# Quadcopter_PCB.net
KiCad netlist of a schematic drawn in EAGLE
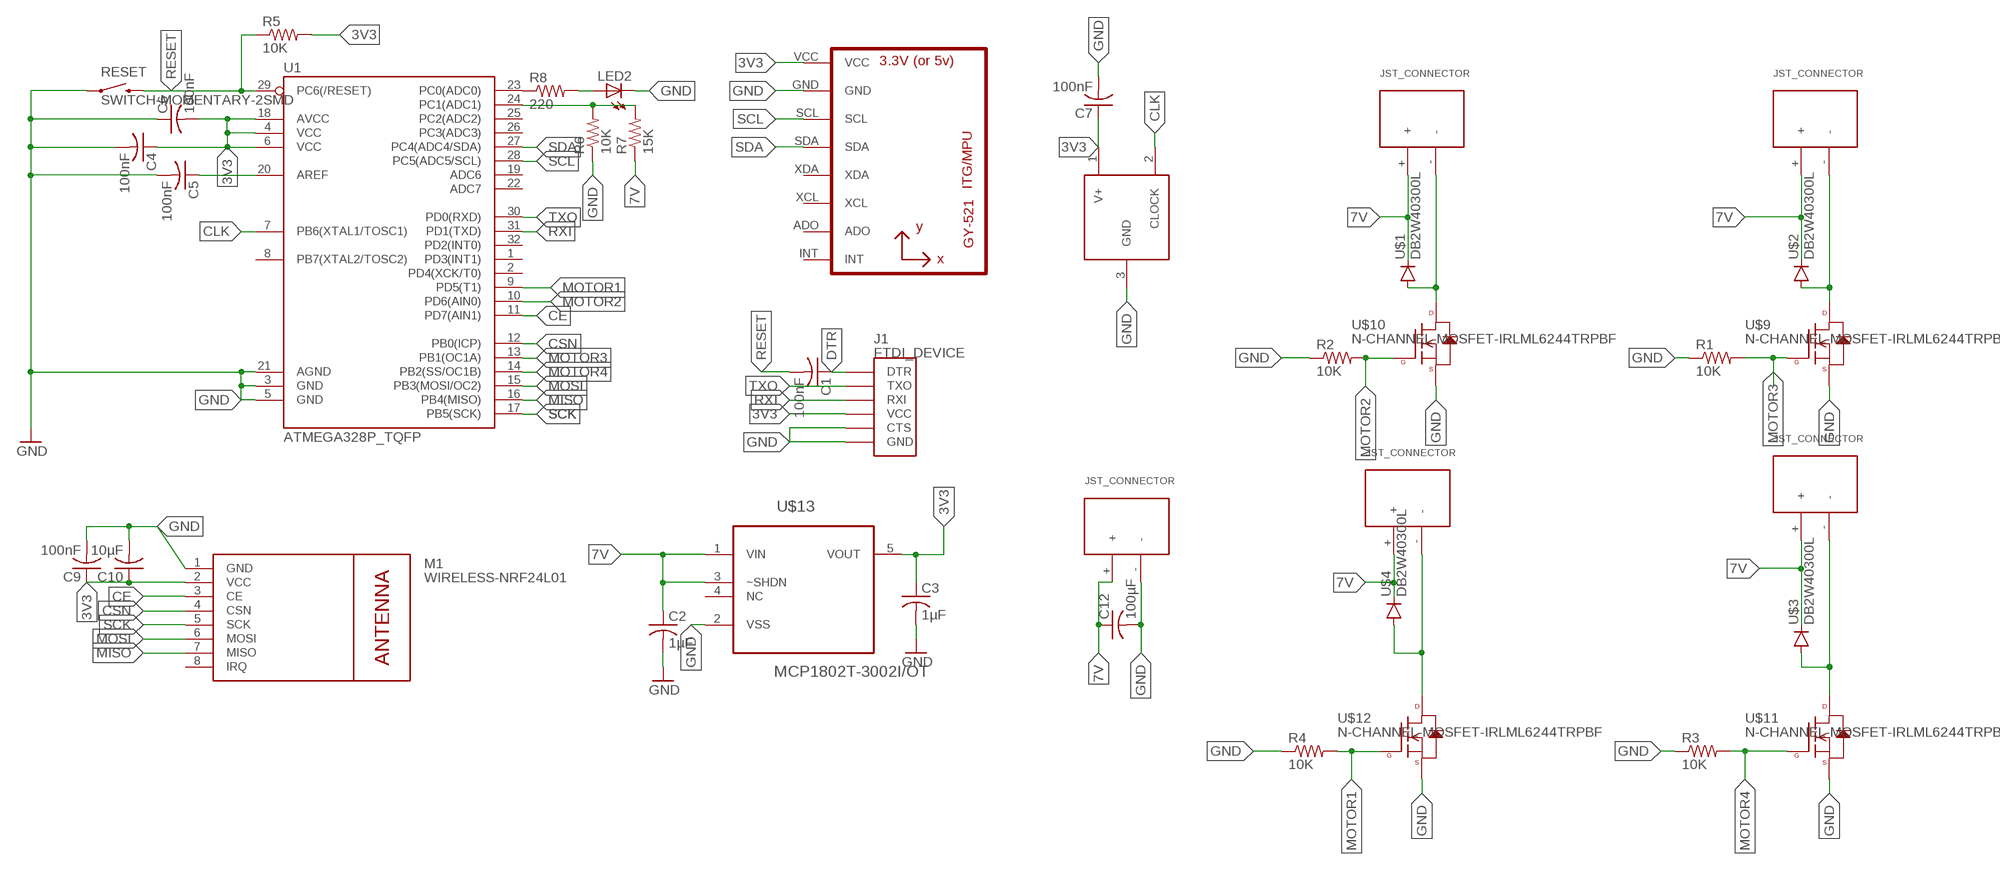
[diagram p0: schematic, sheet 1]

(export (version "E")
  (design (tool "Eeschema 10.0.6"))
  (components
    (comp (ref "AXR1")
      (value "MAX7375")
      (footprint "eagle-import:SC70-3L")
      (libsource (lib "eagle-import") (part "MAX7375"))
    )
    (comp (ref "BATTERYJSTCONNECTOR")
      (value "JST_CONNECTOR_FEMALE")
      (footprint "eagle-import:JST_CONNECTOR_FEMALE")
      (libsource (lib "eagle-import") (part "JST_CONNECTOR_FEMALE"))
    )
    (comp (ref "C1")
      (value "100nF")
      (footprint "eagle-import:C0603")
      (libsource (lib "eagle-import") (part "C-USC0603"))
    )
    (comp (ref "C2")
      (value "1µF")
      (footprint "eagle-import:C0603")
      (libsource (lib "eagle-import") (part "C-USC0603"))
    )
    (comp (ref "C3")
      (value "1µF")
      (footprint "eagle-import:C0603")
      (libsource (lib "eagle-import") (part "C-USC0603"))
    )
    (comp (ref "C4")
      (value "100nF")
      (footprint "eagle-import:C0603")
      (libsource (lib "eagle-import") (part "resistor_C-USC0603"))
    )
    (comp (ref "C5")
      (value "100nF")
      (footprint "eagle-import:C0603")
      (libsource (lib "eagle-import") (part "resistor_C-USC0603"))
    )
    (comp (ref "C6")
      (value "100nF")
      (footprint "eagle-import:C0603")
      (libsource (lib "eagle-import") (part "C-USC0603"))
    )
    (comp (ref "C7")
      (value "100nF")
      (footprint "eagle-import:C0603")
      (libsource (lib "eagle-import") (part "C-USC0603"))
    )
    (comp (ref "C9")
      (value "100nF")
      (footprint "eagle-import:C0603")
      (libsource (lib "eagle-import") (part "C-USC0603"))
    )
    (comp (ref "C10")
      (value "10µF")
      (footprint "eagle-import:C0603")
      (libsource (lib "eagle-import") (part "C-USC0603"))
    )
    (comp (ref "C12")
      (value "100µF")
      (footprint "eagle-import:C1210")
      (libsource (lib "eagle-import") (part "resistor_C-USC1210"))
    )
    (comp (ref "J1")
      (value "FTDI_DEVICE")
      (footprint "eagle-import:FTDI_DEVICE_SIDE")
      (libsource (lib "eagle-import") (part "FTDI_DEVICE"))
    )
    (comp (ref "LED2")
      (value "LEDCHIP-LED0603")
      (footprint "eagle-import:CHIP-LED0603")
      (libsource (lib "eagle-import") (part "LEDCHIP-LED0603"))
    )
    (comp (ref "M1")
      (value "WIRELESS-NRF24L01")
      (footprint "eagle-import:WIRELESS-NRF24L01")
      (libsource (lib "eagle-import") (part "WIRELESS-NRF24L01"))
    )
    (comp (ref "R1")
      (value "10K")
      (footprint "eagle-import:R0603")
      (libsource (lib "eagle-import") (part "R-US_R0603"))
    )
    (comp (ref "R2")
      (value "10K")
      (footprint "eagle-import:R0603")
      (libsource (lib "eagle-import") (part "R-US_R0603"))
    )
    (comp (ref "R3")
      (value "10K")
      (footprint "eagle-import:R0603")
      (libsource (lib "eagle-import") (part "R-US_R0603"))
    )
    (comp (ref "R4")
      (value "10K")
      (footprint "eagle-import:R0603")
      (libsource (lib "eagle-import") (part "R-US_R0603"))
    )
    (comp (ref "R5")
      (value "10K")
      (footprint "eagle-import:R0603")
      (libsource (lib "eagle-import") (part "R-US_R0603"))
    )
    (comp (ref "R6")
      (value "10K")
      (footprint "eagle-import:R0603")
      (libsource (lib "eagle-import") (part "resistor_R-US_R0603"))
    )
    (comp (ref "R7")
      (value "15K")
      (footprint "eagle-import:R0603")
      (libsource (lib "eagle-import") (part "resistor_R-US_R0603"))
    )
    (comp (ref "R8")
      (value "220")
      (footprint "eagle-import:R0603")
      (libsource (lib "eagle-import") (part "R-US_R0603"))
    )
    (comp (ref "RESET")
      (value "SWITCH-MOMENTARY-2SMD")
      (footprint "eagle-import:TACTILE-SWITCH-SMD")
      (libsource (lib "eagle-import") (part "SWITCH-MOMENTARY-2SMD"))
    )
    (comp (ref "U$1")
      (value "DB2W40300L")
      (footprint "eagle-import:MINI2-F3-B")
      (libsource (lib "eagle-import") (part "DB2W40300L"))
    )
    (comp (ref "U$2")
      (value "DB2W40300L")
      (footprint "eagle-import:MINI2-F3-B")
      (libsource (lib "eagle-import") (part "DB2W40300L"))
    )
    (comp (ref "U$3")
      (value "DB2W40300L")
      (footprint "eagle-import:MINI2-F3-B")
      (libsource (lib "eagle-import") (part "DB2W40300L"))
    )
    (comp (ref "U$4")
      (value "DB2W40300L")
      (footprint "eagle-import:MINI2-F3-B")
      (libsource (lib "eagle-import") (part "DB2W40300L"))
    )
    (comp (ref "U$5")
      (value "JST_CONNECTOR_FEMALE")
      (footprint "eagle-import:JST_CONNECTOR_FEMALE")
      (libsource (lib "eagle-import") (part "JST_CONNECTOR_FEMALE"))
    )
    (comp (ref "U$6")
      (value "JST_CONNECTOR_FEMALE")
      (footprint "eagle-import:JST_CONNECTOR_FEMALE")
      (libsource (lib "eagle-import") (part "JST_CONNECTOR_FEMALE"))
    )
    (comp (ref "U$7")
      (value "JST_CONNECTOR_FEMALE")
      (footprint "eagle-import:JST_CONNECTOR_FEMALE")
      (libsource (lib "eagle-import") (part "JST_CONNECTOR_FEMALE"))
    )
    (comp (ref "U$8")
      (value "JST_CONNECTOR_FEMALE")
      (footprint "eagle-import:JST_CONNECTOR_FEMALE")
      (libsource (lib "eagle-import") (part "JST_CONNECTOR_FEMALE"))
    )
    (comp (ref "U$9")
      (value "N-CHANNEL-MOSFET-IRLML6244TRPBF")
      (footprint "eagle-import:SOT23-3")
      (libsource (lib "eagle-import") (part "N-CHANNEL-MOSFET-IRLML6244TRPBF"))
    )
    (comp (ref "U$10")
      (value "N-CHANNEL-MOSFET-IRLML6244TRPBF")
      (footprint "eagle-import:SOT23-3")
      (libsource (lib "eagle-import") (part "N-CHANNEL-MOSFET-IRLML6244TRPBF"))
    )
    (comp (ref "U$11")
      (value "N-CHANNEL-MOSFET-IRLML6244TRPBF")
      (footprint "eagle-import:SOT23-3")
      (libsource (lib "eagle-import") (part "N-CHANNEL-MOSFET-IRLML6244TRPBF"))
    )
    (comp (ref "U$12")
      (value "N-CHANNEL-MOSFET-IRLML6244TRPBF")
      (footprint "eagle-import:SOT23-3")
      (libsource (lib "eagle-import") (part "N-CHANNEL-MOSFET-IRLML6244TRPBF"))
    )
    (comp (ref "U$13")
      (value "MCP1802T-3002I/OT")
      (footprint "eagle-import:SOT95P270X145-5N")
      (libsource (lib "eagle-import") (part "MCP1802T-3002I/OT"))
    )
    (comp (ref "U1")
      (value "ATMEGA328P_TQFP")
      (footprint "eagle-import:TQFP32-08")
      (libsource (lib "eagle-import") (part "ATMEGA328P_TQFP"))
    )
    (comp (ref "U2")
      (value "GY-521MPU6050")
      (footprint "eagle-import:GY-521")
      (libsource (lib "eagle-import") (part "GY-521MPU6050"))
    )
  )
  (nets
    (net (code "1") (name "3V3") (class "Default")
      (node (ref "AXR1") (pin "1") (pinfunction "V+_1") (pintype "bidirectional"))
      (node (ref "C10") (pin "1") (pinfunction "1_1") (pintype "passive"))
      (node (ref "C3") (pin "1") (pinfunction "1_1") (pintype "passive"))
      (node (ref "C4") (pin "1") (pinfunction "1_1") (pintype "passive"))
      (node (ref "C5") (pin "1") (pinfunction "1_1") (pintype "passive"))
      (node (ref "C6") (pin "2") (pinfunction "2_2") (pintype "passive"))
      (node (ref "C7") (pin "1") (pinfunction "1_1") (pintype "passive"))
      (node (ref "C9") (pin "1") (pinfunction "1_1") (pintype "passive"))
      (node (ref "J1") (pin "P$4") (pinfunction "VCC_P$4") (pintype "bidirectional"))
      (node (ref "M1") (pin "2") (pinfunction "VCC_2") (pintype "power_in"))
      (node (ref "R5") (pin "2") (pinfunction "2_2") (pintype "passive"))
      (node (ref "U$13") (pin "5") (pinfunction "VOUT_5") (pintype "output"))
      (node (ref "U1") (pin "18") (pinfunction "AVCC_18") (pintype "bidirectional"))
      (node (ref "U1") (pin "20") (pinfunction "AREF_20") (pintype "bidirectional"))
      (node (ref "U1") (pin "4") (pinfunction "VCC_4") (pintype "bidirectional"))
      (node (ref "U1") (pin "6") (pinfunction "VCC_6") (pintype "bidirectional"))
      (node (ref "U2") (pin "VCC") (pinfunction "VCC_VCC") (pintype "bidirectional"))
    )
    (net (code "2") (name "7V") (class "Default")
      (node (ref "BATTERYJSTCONNECTOR") (pin "+") (pinfunction "+_+") (pintype "bidirectional"))
      (node (ref "C12") (pin "1") (pinfunction "1_1") (pintype "passive"))
      (node (ref "C2") (pin "1") (pinfunction "1_1") (pintype "passive"))
      (node (ref "R7") (pin "1") (pinfunction "1_1") (pintype "passive"))
      (node (ref "U$1") (pin "NEG") (pinfunction "GPIN_NEG") (pintype "passive"))
      (node (ref "U$13") (pin "1") (pinfunction "VIN_1") (pintype "power_in"))
      (node (ref "U$13") (pin "3") (pinfunction "~{SHDN}_3") (pintype "input"))
      (node (ref "U$2") (pin "NEG") (pinfunction "GPIN_NEG") (pintype "passive"))
      (node (ref "U$3") (pin "NEG") (pinfunction "GPIN_NEG") (pintype "passive"))
      (node (ref "U$4") (pin "NEG") (pinfunction "GPIN_NEG") (pintype "passive"))
      (node (ref "U$5") (pin "+") (pinfunction "+_+") (pintype "bidirectional"))
      (node (ref "U$6") (pin "+") (pinfunction "+_+") (pintype "bidirectional"))
      (node (ref "U$7") (pin "+") (pinfunction "+_+") (pintype "bidirectional"))
      (node (ref "U$8") (pin "+") (pinfunction "+_+") (pintype "bidirectional"))
    )
    (net (code "3") (name "CE") (class "Default")
      (node (ref "M1") (pin "3") (pinfunction "CE_3") (pintype "bidirectional"))
      (node (ref "U1") (pin "11") (pinfunction "PD7(AIN1)_11") (pintype "bidirectional"))
    )
    (net (code "4") (name "CLK") (class "Default")
      (node (ref "AXR1") (pin "2") (pinfunction "CLOCK_2") (pintype "bidirectional"))
      (node (ref "U1") (pin "7") (pinfunction "PB6(XTAL1/TOSC1)_7") (pintype "bidirectional"))
    )
    (net (code "5") (name "CSN") (class "Default")
      (node (ref "M1") (pin "4") (pinfunction "CSN_4") (pintype "bidirectional"))
      (node (ref "U1") (pin "12") (pinfunction "PB0(ICP)_12") (pintype "bidirectional"))
    )
    (net (code "6") (name "DTR") (class "Default")
      (node (ref "C1") (pin "1") (pinfunction "1_1") (pintype "passive"))
      (node (ref "J1") (pin "P$1") (pinfunction "DTR_P$1") (pintype "bidirectional"))
    )
    (net (code "7") (name "GND") (class "Default")
      (node (ref "AXR1") (pin "3") (pinfunction "GND_3") (pintype "bidirectional"))
      (node (ref "BATTERYJSTCONNECTOR") (pin "-") (pinfunction "-_-") (pintype "bidirectional"))
      (node (ref "C10") (pin "2") (pinfunction "2_2") (pintype "passive"))
      (node (ref "C12") (pin "2") (pinfunction "2_2") (pintype "passive"))
      (node (ref "C2") (pin "2") (pinfunction "2_2") (pintype "passive"))
      (node (ref "C3") (pin "2") (pinfunction "2_2") (pintype "passive"))
      (node (ref "C4") (pin "2") (pinfunction "2_2") (pintype "passive"))
      (node (ref "C5") (pin "2") (pinfunction "2_2") (pintype "passive"))
      (node (ref "C6") (pin "1") (pinfunction "1_1") (pintype "passive"))
      (node (ref "C7") (pin "2") (pinfunction "2_2") (pintype "passive"))
      (node (ref "C9") (pin "2") (pinfunction "2_2") (pintype "passive"))
      (node (ref "J1") (pin "P$5") (pinfunction "CTS_P$5") (pintype "bidirectional"))
      (node (ref "J1") (pin "P$6") (pinfunction "GND_P$6") (pintype "bidirectional"))
      (node (ref "LED2") (pin "C") (pinfunction "C_C") (pintype "passive"))
      (node (ref "M1") (pin "1") (pinfunction "GND_1") (pintype "power_in"))
      (node (ref "R1") (pin "1") (pinfunction "1_1") (pintype "passive"))
      (node (ref "R2") (pin "1") (pinfunction "1_1") (pintype "passive"))
      (node (ref "R3") (pin "1") (pinfunction "1_1") (pintype "passive"))
      (node (ref "R4") (pin "1") (pinfunction "1_1") (pintype "passive"))
      (node (ref "R6") (pin "1") (pinfunction "1_1") (pintype "passive"))
      (node (ref "RESET") (pin "1") (pinfunction "1_1") (pintype "passive"))
      (node (ref "U$10") (pin "2") (pinfunction "S_2") (pintype "passive"))
      (node (ref "U$11") (pin "2") (pinfunction "S_2") (pintype "passive"))
      (node (ref "U$12") (pin "2") (pinfunction "S_2") (pintype "passive"))
      (node (ref "U$13") (pin "2") (pinfunction "VSS_2") (pintype "passive"))
      (node (ref "U$9") (pin "2") (pinfunction "S_2") (pintype "passive"))
      (node (ref "U1") (pin "21") (pinfunction "AGND_21") (pintype "bidirectional"))
      (node (ref "U1") (pin "3") (pinfunction "GND_3") (pintype "bidirectional"))
      (node (ref "U1") (pin "5") (pinfunction "GND_5") (pintype "bidirectional"))
      (node (ref "U2") (pin "GND") (pinfunction "GND_GND") (pintype "bidirectional"))
    )
    (net (code "8") (name "MISO") (class "Default")
      (node (ref "M1") (pin "7") (pinfunction "MISO_7") (pintype "bidirectional"))
      (node (ref "U1") (pin "16") (pinfunction "PB4(MISO)_16") (pintype "bidirectional"))
    )
    (net (code "9") (name "MOSI") (class "Default")
      (node (ref "M1") (pin "6") (pinfunction "MOSI_6") (pintype "bidirectional"))
      (node (ref "U1") (pin "15") (pinfunction "PB3(MOSI/OC2)_15") (pintype "bidirectional"))
    )
    (net (code "10") (name "MOTOR1") (class "Default")
      (node (ref "R4") (pin "2") (pinfunction "2_2") (pintype "passive"))
      (node (ref "U$12") (pin "1") (pinfunction "G_1") (pintype "passive"))
      (node (ref "U1") (pin "9") (pinfunction "PD5(T1)_9") (pintype "bidirectional"))
    )
    (net (code "11") (name "MOTOR2") (class "Default")
      (node (ref "R2") (pin "2") (pinfunction "2_2") (pintype "passive"))
      (node (ref "U$10") (pin "1") (pinfunction "G_1") (pintype "passive"))
      (node (ref "U1") (pin "10") (pinfunction "PD6(AIN0)_10") (pintype "bidirectional"))
    )
    (net (code "12") (name "MOTOR3") (class "Default")
      (node (ref "R1") (pin "2") (pinfunction "2_2") (pintype "passive"))
      (node (ref "U$9") (pin "1") (pinfunction "G_1") (pintype "passive"))
      (node (ref "U1") (pin "13") (pinfunction "PB1(OC1A)_13") (pintype "bidirectional"))
    )
    (net (code "13") (name "MOTOR4") (class "Default")
      (node (ref "R3") (pin "2") (pinfunction "2_2") (pintype "passive"))
      (node (ref "U$11") (pin "1") (pinfunction "G_1") (pintype "passive"))
      (node (ref "U1") (pin "14") (pinfunction "PB2(SS/OC1B)_14") (pintype "bidirectional"))
    )
    (net (code "14") (name "Net-(LED2-PadA)") (class "Default")
      (node (ref "LED2") (pin "A") (pinfunction "A_A") (pintype "passive"))
      (node (ref "R8") (pin "2") (pinfunction "2_2") (pintype "passive"))
    )
    (net (code "15") (name "Net-(U$1-PPIN)") (class "Default")
      (node (ref "U$1") (pin "POS") (pinfunction "PPIN_POS") (pintype "passive"))
      (node (ref "U$10") (pin "3") (pinfunction "D_3") (pintype "passive"))
      (node (ref "U$6") (pin "-") (pinfunction "-_-") (pintype "bidirectional"))
    )
    (net (code "16") (name "Net-(U$2-PPIN)") (class "Default")
      (node (ref "U$2") (pin "POS") (pinfunction "PPIN_POS") (pintype "passive"))
      (node (ref "U$7") (pin "-") (pinfunction "-_-") (pintype "bidirectional"))
      (node (ref "U$9") (pin "3") (pinfunction "D_3") (pintype "passive"))
    )
    (net (code "17") (name "Net-(U$11-D)") (class "Default")
      (node (ref "U$11") (pin "3") (pinfunction "D_3") (pintype "passive"))
      (node (ref "U$3") (pin "POS") (pinfunction "PPIN_POS") (pintype "passive"))
      (node (ref "U$8") (pin "-") (pinfunction "-_-") (pintype "bidirectional"))
    )
    (net (code "18") (name "Net-(U$12-D)") (class "Default")
      (node (ref "U$12") (pin "3") (pinfunction "D_3") (pintype "passive"))
      (node (ref "U$4") (pin "POS") (pinfunction "PPIN_POS") (pintype "passive"))
      (node (ref "U$5") (pin "-") (pinfunction "-_-") (pintype "bidirectional"))
    )
    (net (code "19") (name "Net-(U1-PC0(ADC0))") (class "Default")
      (node (ref "R8") (pin "1") (pinfunction "1_1") (pintype "passive"))
      (node (ref "U1") (pin "23") (pinfunction "PC0(ADC0)_23") (pintype "bidirectional"))
    )
    (net (code "20") (name "Net-(U1-PC1(ADC1))") (class "Default")
      (node (ref "R6") (pin "2") (pinfunction "2_2") (pintype "passive"))
      (node (ref "R7") (pin "2") (pinfunction "2_2") (pintype "passive"))
      (node (ref "U1") (pin "24") (pinfunction "PC1(ADC1)_24") (pintype "bidirectional"))
    )
    (net (code "21") (name "RESET") (class "Default")
      (node (ref "C1") (pin "2") (pinfunction "2_2") (pintype "passive"))
      (node (ref "R5") (pin "1") (pinfunction "1_1") (pintype "passive"))
      (node (ref "RESET") (pin "3") (pinfunction "2_3") (pintype "passive"))
      (node (ref "U1") (pin "29") (pinfunction "PC6(/RESET)_29") (pintype "bidirectional"))
    )
    (net (code "22") (name "RXI") (class "Default")
      (node (ref "J1") (pin "P$3") (pinfunction "RXI_P$3") (pintype "bidirectional"))
      (node (ref "U1") (pin "31") (pinfunction "PD1(TXD)_31") (pintype "bidirectional"))
    )
    (net (code "23") (name "SCK") (class "Default")
      (node (ref "M1") (pin "5") (pinfunction "SCK_5") (pintype "bidirectional"))
      (node (ref "U1") (pin "17") (pinfunction "PB5(SCK)_17") (pintype "bidirectional"))
    )
    (net (code "24") (name "SCL") (class "Default")
      (node (ref "U1") (pin "28") (pinfunction "PC5(ADC5/SCL)_28") (pintype "bidirectional"))
      (node (ref "U2") (pin "SCL") (pinfunction "SCL_SCL") (pintype "bidirectional"))
    )
    (net (code "25") (name "SDA") (class "Default")
      (node (ref "U1") (pin "27") (pinfunction "PC4(ADC4/SDA)_27") (pintype "bidirectional"))
      (node (ref "U2") (pin "SDA") (pinfunction "SDA_SDA") (pintype "bidirectional"))
    )
    (net (code "26") (name "TXO") (class "Default")
      (node (ref "J1") (pin "P$2") (pinfunction "TXO_P$2") (pintype "bidirectional"))
      (node (ref "U1") (pin "30") (pinfunction "PD0(RXD)_30") (pintype "bidirectional"))
    )
    (net (code "27") (name "unconnected-(M1-IRQ-Pad8)") (class "Default")
      (node (ref "M1") (pin "8") (pinfunction "IRQ_8") (pintype "bidirectional"))
    )
    (net (code "28") (name "unconnected-(U$13-NC-Pad4)") (class "Default")
      (node (ref "U$13") (pin "4") (pinfunction "NC_4") (pintype "no_connect"))
    )
    (net (code "29") (name "unconnected-(U1-ADC6-Pad19)") (class "Default")
      (node (ref "U1") (pin "19") (pinfunction "ADC6_19") (pintype "bidirectional"))
    )
    (net (code "30") (name "unconnected-(U1-ADC7-Pad22)") (class "Default")
      (node (ref "U1") (pin "22") (pinfunction "ADC7_22") (pintype "bidirectional"))
    )
    (net (code "31") (name "unconnected-(U1-PB7(XTAL2{slash}TOSC2)-Pad8)") (class "Default")
      (node (ref "U1") (pin "8") (pinfunction "PB7(XTAL2/TOSC2)_8") (pintype "bidirectional"))
    )
    (net (code "32") (name "unconnected-(U1-PC2(ADC2)-Pad25)") (class "Default")
      (node (ref "U1") (pin "25") (pinfunction "PC2(ADC2)_25") (pintype "bidirectional"))
    )
    (net (code "33") (name "unconnected-(U1-PC3(ADC3)-Pad26)") (class "Default")
      (node (ref "U1") (pin "26") (pinfunction "PC3(ADC3)_26") (pintype "bidirectional"))
    )
    (net (code "34") (name "unconnected-(U1-PD2(INT0)-Pad32)") (class "Default")
      (node (ref "U1") (pin "32") (pinfunction "PD2(INT0)_32") (pintype "bidirectional"))
    )
    (net (code "35") (name "unconnected-(U1-PD3(INT1)-Pad1)") (class "Default")
      (node (ref "U1") (pin "1") (pinfunction "PD3(INT1)_1") (pintype "bidirectional"))
    )
    (net (code "36") (name "unconnected-(U1-PD4(XCK{slash}T0)-Pad2)") (class "Default")
      (node (ref "U1") (pin "2") (pinfunction "PD4(XCK/T0)_2") (pintype "bidirectional"))
    )
    (net (code "37") (name "unconnected-(U2-PadADO)") (class "Default")
      (node (ref "U2") (pin "ADO") (pinfunction "ADO_ADO") (pintype "bidirectional"))
    )
    (net (code "38") (name "unconnected-(U2-PadINT)") (class "Default")
      (node (ref "U2") (pin "INT") (pinfunction "INT_INT") (pintype "bidirectional"))
    )
    (net (code "39") (name "unconnected-(U2-PadXCL)") (class "Default")
      (node (ref "U2") (pin "XCL") (pinfunction "XCL_XCL") (pintype "bidirectional"))
    )
    (net (code "40") (name "unconnected-(U2-PadXDA)") (class "Default")
      (node (ref "U2") (pin "XDA") (pinfunction "XDA_XDA") (pintype "bidirectional"))
    )
  )
)
